# LWOC_PCB_2v1.net
KiCad netlist of a schematic drawn in EAGLE
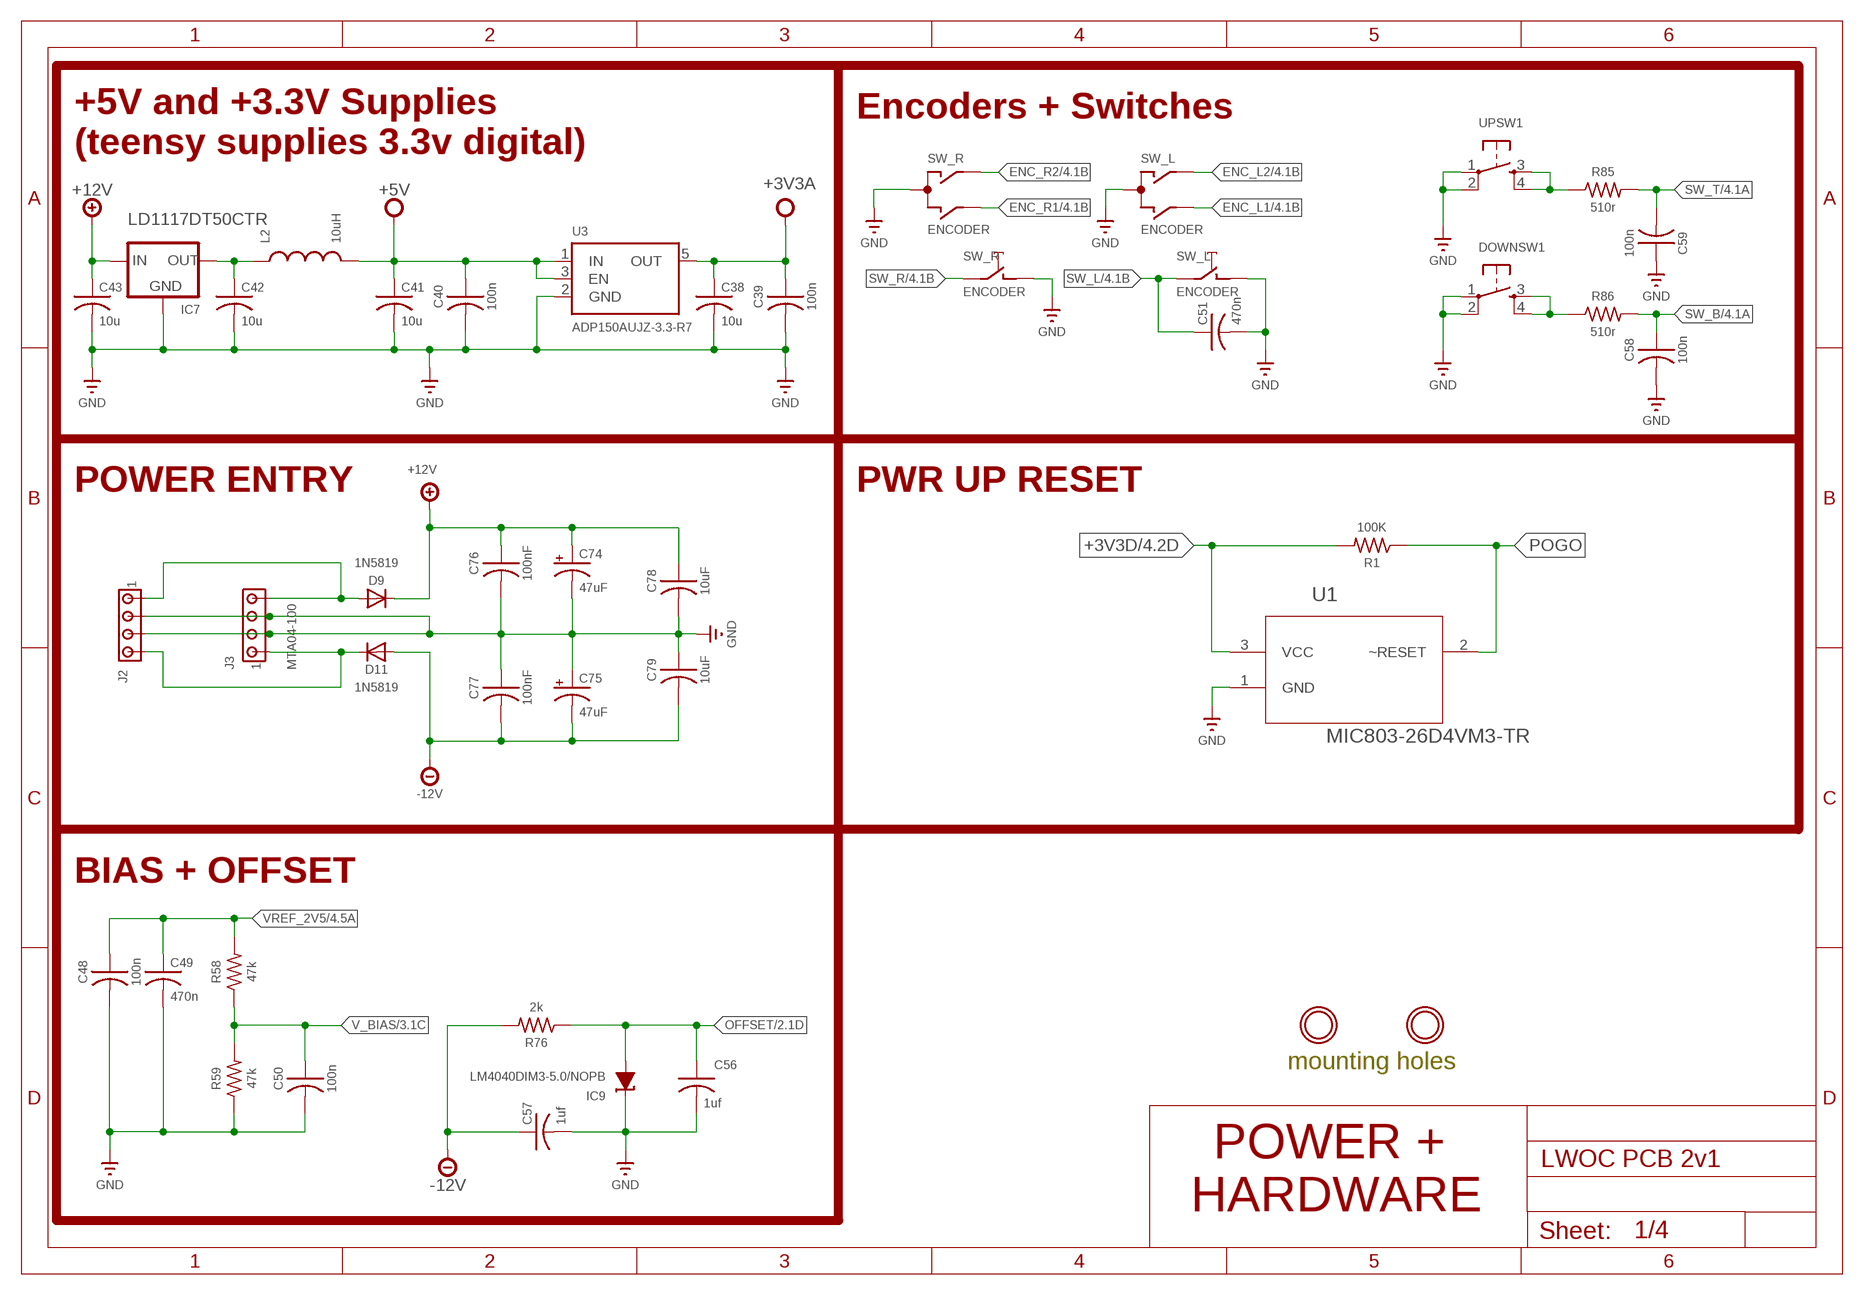
[diagram p0: schematic, sheet 1]
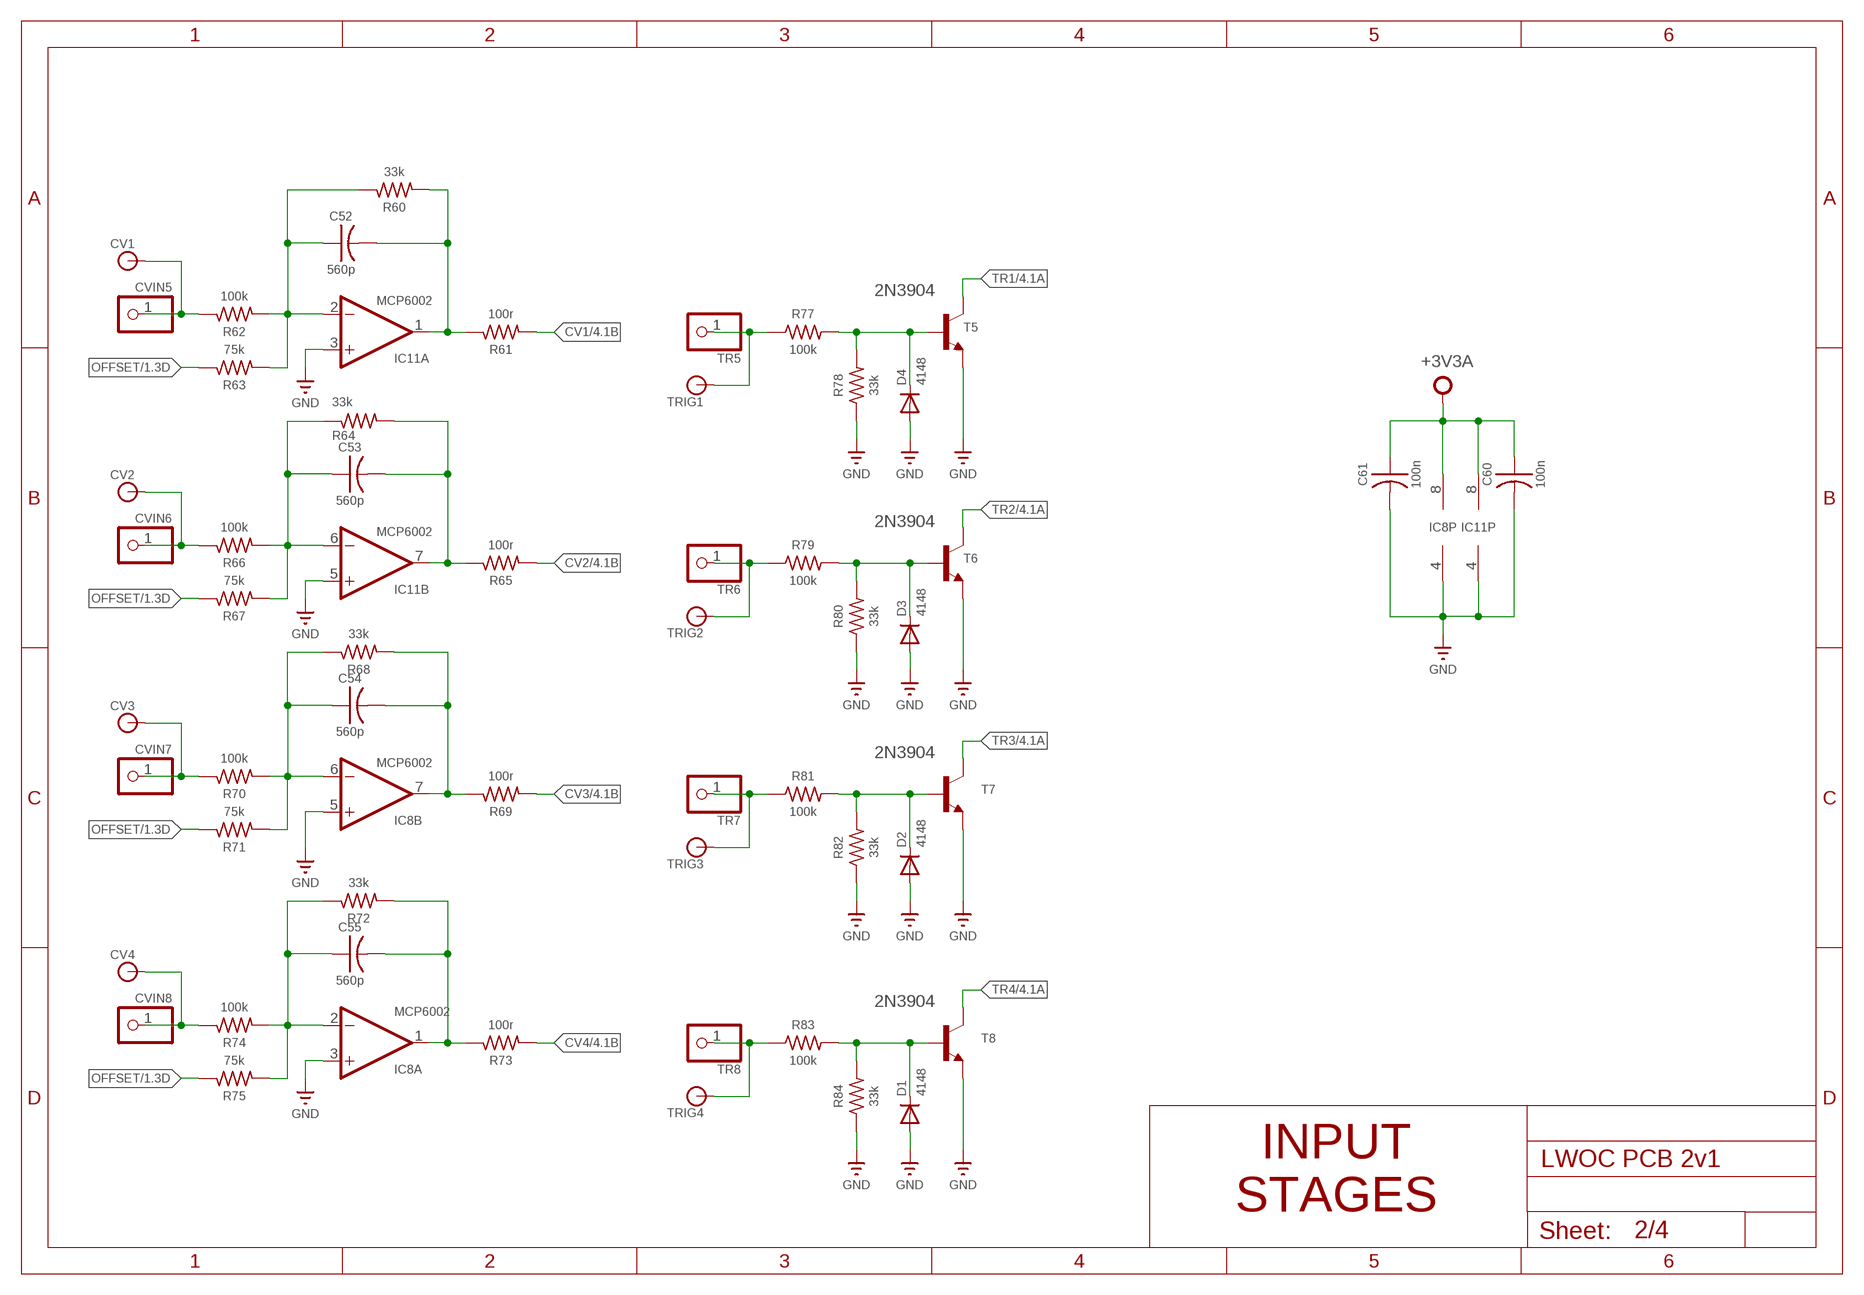
[diagram p1: schematic, sheet 2]
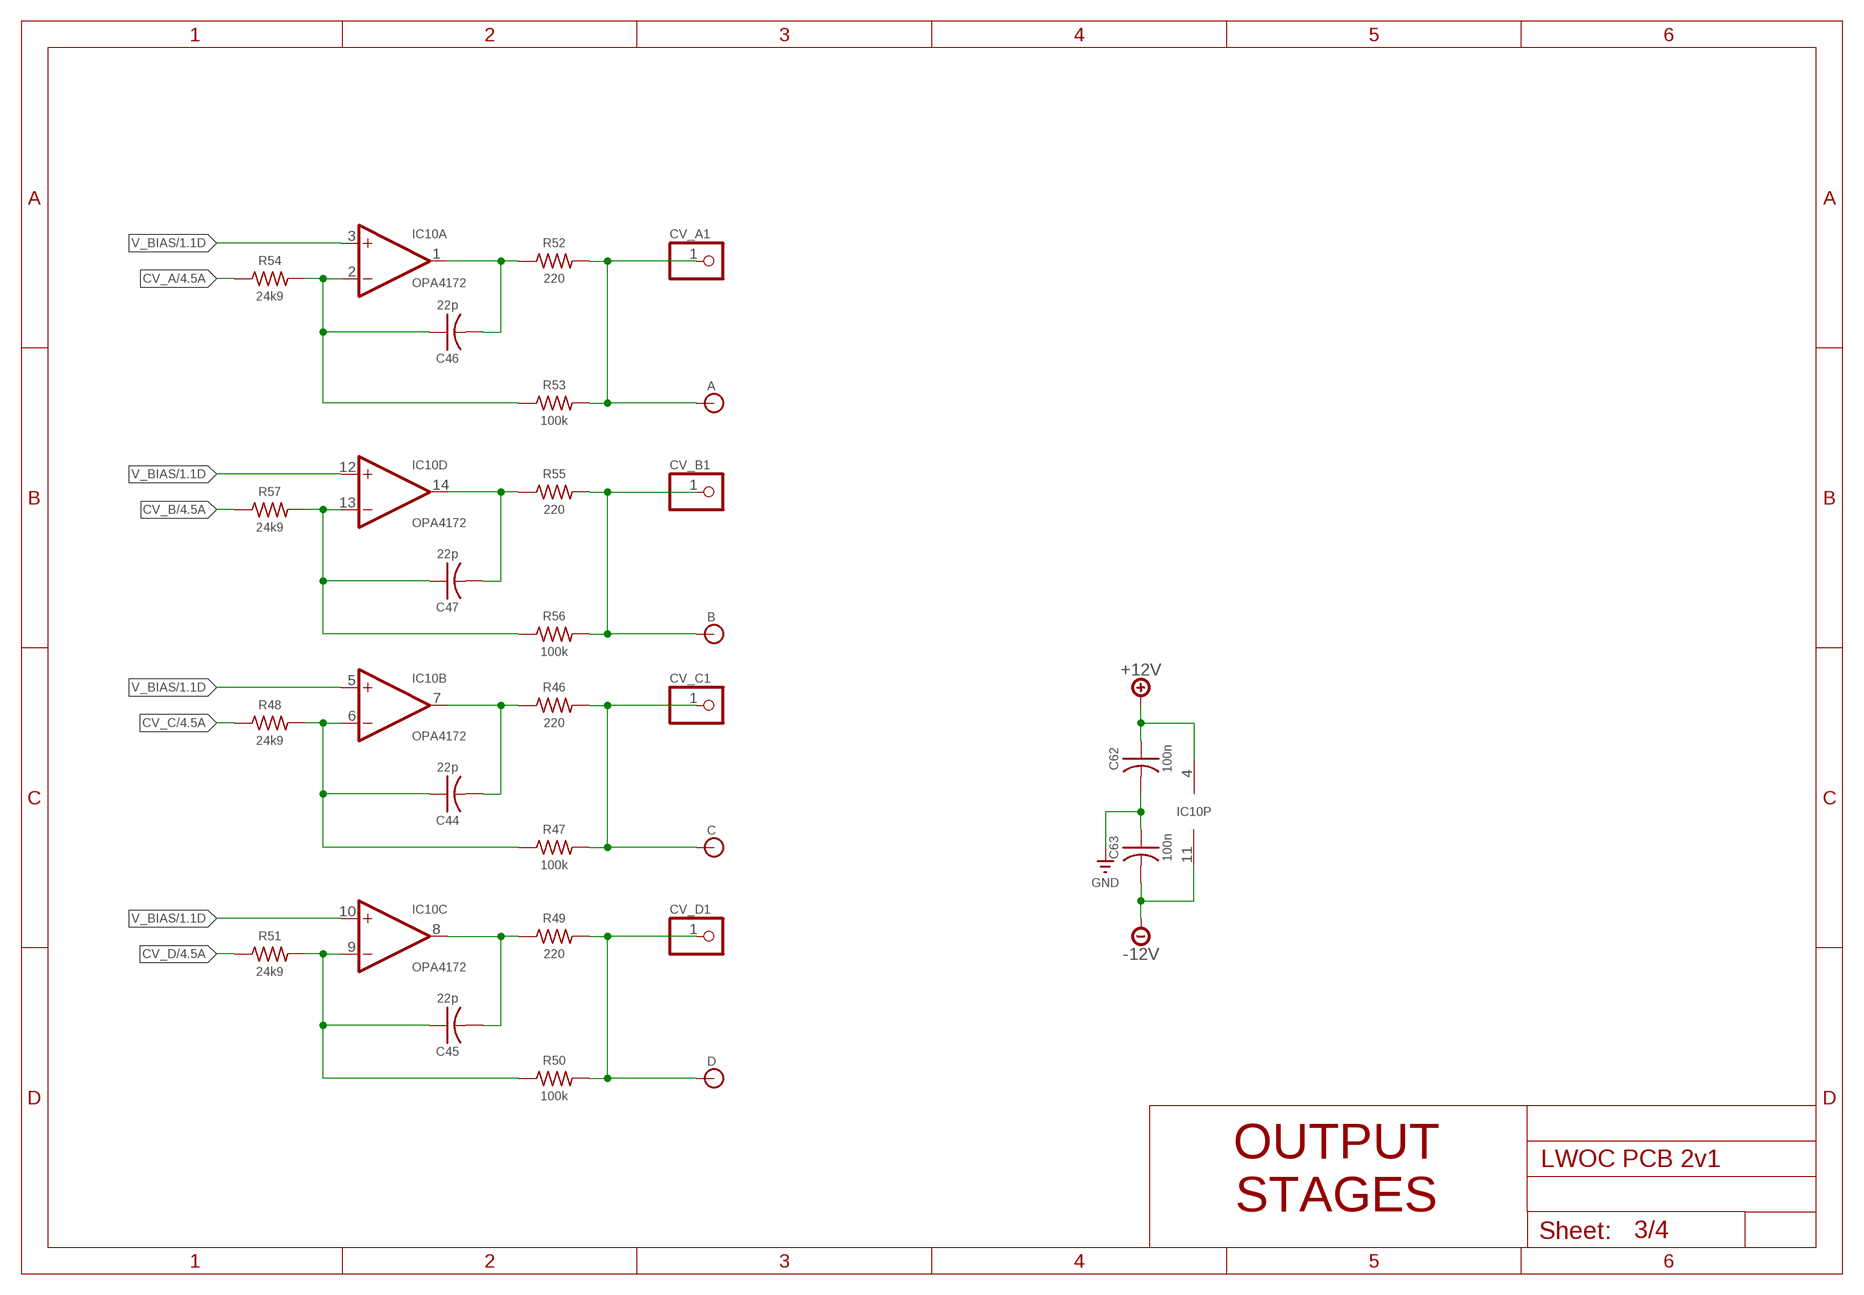
[diagram p2: schematic, sheet 3]
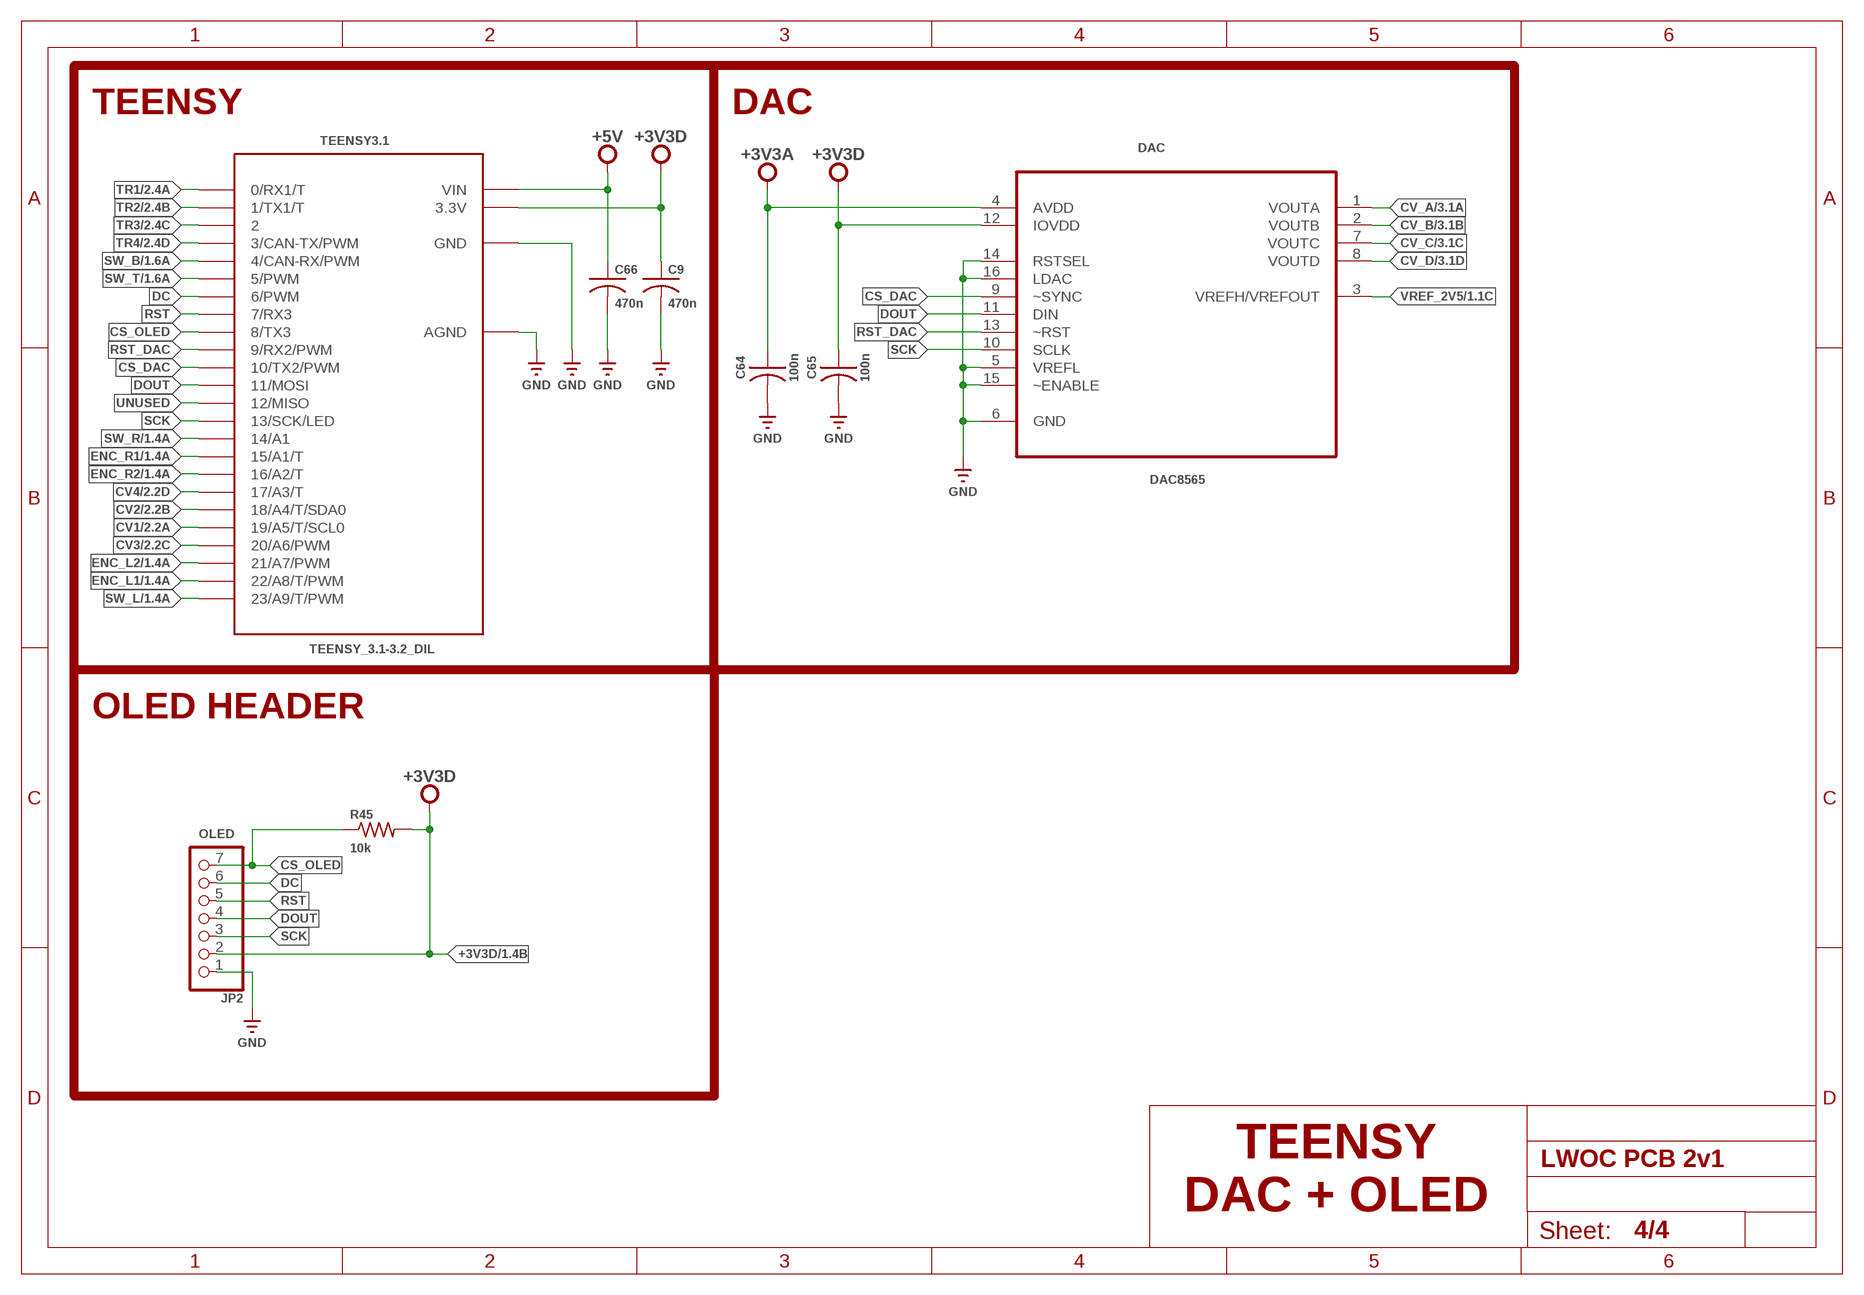
[diagram p3: schematic, sheet 4]

(export (version "E")
  (design (tool "Eeschema 10.0.6"))
  (components
    (comp (ref "C38")
      (value "10u")
      (footprint "eagle-import:C1206K")
      (libsource (lib "eagle-import") (part "C-USC1206K"))
    )
    (comp (ref "C39")
      (value "100n")
      (footprint "eagle-import:RCL_C0603K")
      (libsource (lib "eagle-import") (part "RCL_C-USC0603K"))
    )
    (comp (ref "C40")
      (value "100n")
      (footprint "eagle-import:RCL_C0603K")
      (libsource (lib "eagle-import") (part "RCL_C-USC0603K"))
    )
    (comp (ref "C41")
      (value "10u")
      (footprint "eagle-import:C1206K")
      (libsource (lib "eagle-import") (part "C-USC1206K"))
    )
    (comp (ref "C42")
      (value "10u")
      (footprint "eagle-import:C1206K")
      (libsource (lib "eagle-import") (part "C-USC1206K"))
    )
    (comp (ref "C43")
      (value "10u")
      (footprint "eagle-import:C1206K")
      (libsource (lib "eagle-import") (part "C-USC1206K"))
    )
    (comp (ref "C48")
      (value "100n")
      (footprint "eagle-import:RCL_C0603K")
      (libsource (lib "eagle-import") (part "RCL_C-USC0603K"))
    )
    (comp (ref "C49")
      (value "470n")
      (footprint "eagle-import:RCL_C0603K")
      (libsource (lib "eagle-import") (part "RCL_C-USC0603K"))
    )
    (comp (ref "C50")
      (value "100n")
      (footprint "eagle-import:RCL_C0603K")
      (libsource (lib "eagle-import") (part "RCL_C-USC0603K"))
    )
    (comp (ref "C51")
      (value "470n")
      (footprint "eagle-import:C0805K")
      (libsource (lib "eagle-import") (part "C-USC0805K"))
    )
    (comp (ref "C56")
      (value "1uf")
      (footprint "eagle-import:C0805K")
      (libsource (lib "eagle-import") (part "C-USC0805K"))
    )
    (comp (ref "C57")
      (value "1uf")
      (footprint "eagle-import:C0805K")
      (libsource (lib "eagle-import") (part "C-USC0805K"))
    )
    (comp (ref "C58")
      (value "100n")
      (footprint "eagle-import:RCL_C0603K")
      (libsource (lib "eagle-import") (part "RCL_C-USC0603K"))
    )
    (comp (ref "C59")
      (value "100n")
      (footprint "eagle-import:RCL_C0603K")
      (libsource (lib "eagle-import") (part "RCL_C-USC0603K"))
    )
    (comp (ref "C74")
      (value "47uF")
      (footprint "eagle-import:RCL_E2,5-6")
      (libsource (lib "eagle-import") (part "RCL_CPOL-USE2.5-6"))
    )
    (comp (ref "C75")
      (value "47uF")
      (footprint "eagle-import:RCL_E2,5-6")
      (libsource (lib "eagle-import") (part "RCL_CPOL-USE2.5-6"))
    )
    (comp (ref "C76")
      (value "100nF")
      (footprint "eagle-import:RCL_C0603K")
      (libsource (lib "eagle-import") (part "ripples_v40_RCL_C-USC0603K"))
    )
    (comp (ref "C77")
      (value "100nF")
      (footprint "eagle-import:RCL_C0603K")
      (libsource (lib "eagle-import") (part "ripples_v40_RCL_C-USC0603K"))
    )
    (comp (ref "C78")
      (value "10uF")
      (footprint "eagle-import:RCL_C1210")
      (libsource (lib "eagle-import") (part "RCL_C-USC1210"))
    )
    (comp (ref "C79")
      (value "10uF")
      (footprint "eagle-import:RCL_C1210")
      (libsource (lib "eagle-import") (part "RCL_C-USC1210"))
    )
    (comp (ref "D9")
      (value "1N5819")
      (footprint "eagle-import:DIODE_SOD323-W")
      (libsource (lib "eagle-import") (part "ripples_v40_DIODE_DIODE-SOD323-W"))
    )
    (comp (ref "D11")
      (value "1N5819")
      (footprint "eagle-import:DIODE_SOD323-W")
      (libsource (lib "eagle-import") (part "ripples_v40_DIODE_DIODE-SOD323-W"))
    )
    (comp (ref "DOWNSW1")
      (value "SPARKFUN_TAC_SWITCHPTH")
      (footprint "eagle-import:SPARKFUN_TACTILE-PTH")
      (libsource (lib "eagle-import") (part "SPARKFUN_TAC_SWITCHPTH"))
    )
    (comp (ref "IC7")
      (value "LD1117DT50CTR")
      (footprint "eagle-import:TO252")
      (libsource (lib "eagle-import") (part "LM1117TO252"))
    )
    (comp (ref "IC9")
      (value "LM4040DIM3-5.0/NOPB")
      (footprint "eagle-import:DBZ_R-PDSO-G3")
      (libsource (lib "eagle-import") (part "LM4041DBZA12"))
    )
    (comp (ref "J2")
      (value "MTA04-156")
      (footprint "eagle-import:1X4MTA")
      (libsource (lib "eagle-import") (part "MTA04-156"))
    )
    (comp (ref "J3")
      (value "MTA04-100")
      (footprint "eagle-import:1X04MTA")
      (libsource (lib "eagle-import") (part "MTA04-100"))
    )
    (comp (ref "L2")
      (value "10uH")
      (footprint "eagle-import:1210")
      (libsource (lib "eagle-import") (part "INDUCTOR1210"))
    )
    (comp (ref "R1")
      (value "100K")
      (footprint "eagle-import:RCL_R0603")
      (libsource (lib "eagle-import") (part "RCL_R-US_R0603"))
    )
    (comp (ref "R58")
      (value "47k")
      (footprint "eagle-import:RCL_R0603")
      (libsource (lib "eagle-import") (part "RCL_R-US_R0603"))
    )
    (comp (ref "R59")
      (value "47k")
      (footprint "eagle-import:RCL_R0603")
      (libsource (lib "eagle-import") (part "RCL_R-US_R0603"))
    )
    (comp (ref "R76")
      (value "2k")
      (footprint "eagle-import:RCL_R0603")
      (libsource (lib "eagle-import") (part "RCL_R-US_R0603"))
    )
    (comp (ref "R85")
      (value "510r")
      (footprint "eagle-import:RCL_R0603")
      (libsource (lib "eagle-import") (part "RCL_R-US_R0603"))
    )
    (comp (ref "R86")
      (value "510r")
      (footprint "eagle-import:RCL_R0603")
      (libsource (lib "eagle-import") (part "RCL_R-US_R0603"))
    )
    (comp (ref "SW_L")
      (value "ENCODER")
      (footprint "eagle-import:OG-ENCODER_ALPS_EC12E_SW")
      (libsource (lib "eagle-import") (part "OG-ENCODER_EC12E_SW"))
    )
    (comp (ref "SW_R")
      (value "ENCODER")
      (footprint "eagle-import:OG-ENCODER_ALPS_EC12E_SW")
      (libsource (lib "eagle-import") (part "OG-ENCODER_EC12E_SW"))
    )
    (comp (ref "U$23")
      (value "MOUNTINGHOLE2.5")
      (footprint "eagle-import:MOUNTINGHOLE_2.5_PLATED")
      (libsource (lib "eagle-import") (part "MOUNTINGHOLE2.5"))
    )
    (comp (ref "U$26")
      (value "MOUNTINGHOLE2.5")
      (footprint "eagle-import:MOUNTINGHOLE_2.5_PLATED")
      (libsource (lib "eagle-import") (part "MOUNTINGHOLE2.5"))
    )
    (comp (ref "U1")
      (value "MIC803-26D4VM3-TR")
      (footprint "eagle-import:SOT95P232X110-3N")
      (fields (field (name "MPN") "MIC803-30D4VM3TR"))
      (libsource (lib "eagle-import") (part "MIC803-30D4VM3TR"))
    )
    (comp (ref "U3")
      (value "ADP150AUJZ-3.3-R7")
      (footprint "eagle-import:SOT23-5")
      (libsource (lib "eagle-import") (part "ADP121"))
    )
    (comp (ref "UPSW1")
      (value "SPARKFUN_TAC_SWITCHPTH")
      (footprint "eagle-import:SPARKFUN_TACTILE-PTH")
      (libsource (lib "eagle-import") (part "SPARKFUN_TAC_SWITCHPTH"))
    )
    (comp (ref "C9")
      (value "470n")
      (footprint "eagle-import:C0805K")
      (libsource (lib "eagle-import") (part "C-USC0805K"))
    )
    (comp (ref "C64")
      (value "100n")
      (footprint "eagle-import:RCL_C0603K")
      (libsource (lib "eagle-import") (part "RCL_C-USC0603K"))
    )
    (comp (ref "C65")
      (value "100n")
      (footprint "eagle-import:RCL_C0603K")
      (libsource (lib "eagle-import") (part "RCL_C-USC0603K"))
    )
    (comp (ref "C66")
      (value "470n")
      (footprint "eagle-import:C0805K")
      (libsource (lib "eagle-import") (part "C-USC0805K"))
    )
    (comp (ref "DAC")
      (value "DAC8565")
      (footprint "eagle-import:SOP65P640X120-16N")
      (fields (field (name "MF") "Texas Instruments") (field (name "MP") "DAC8565IAPW"))
      (libsource (lib "eagle-import") (part "DAC8565IAPW"))
    )
    (comp (ref "JP2")
      (value "OLED")
      (footprint "eagle-import:1X07-S")
      (libsource (lib "eagle-import") (part "PINHD-1X07_2.54-S"))
    )
    (comp (ref "R45")
      (value "10k")
      (footprint "eagle-import:M0805")
      (libsource (lib "eagle-import") (part "R-US_M0805"))
    )
    (comp (ref "TEENSY3.1")
      (value "TEENSY_3.1-3.2_DIL")
      (footprint "eagle-import:TEENSY_3.0-3.2&LC_DIL")
      (libsource (lib "eagle-import") (part "TEENSY_3.1-3.2_DIL"))
    )
    (comp (ref "C52")
      (value "560p")
      (footprint "eagle-import:RCL_C0603K")
      (libsource (lib "eagle-import") (part "RCL_C-USC0603K"))
    )
    (comp (ref "C53")
      (value "560p")
      (footprint "eagle-import:RCL_C0603K")
      (libsource (lib "eagle-import") (part "RCL_C-USC0603K"))
    )
    (comp (ref "C54")
      (value "560p")
      (footprint "eagle-import:RCL_C0603K")
      (libsource (lib "eagle-import") (part "RCL_C-USC0603K"))
    )
    (comp (ref "C55")
      (value "560p")
      (footprint "eagle-import:RCL_C0603K")
      (libsource (lib "eagle-import") (part "RCL_C-USC0603K"))
    )
    (comp (ref "C60")
      (value "100n")
      (footprint "eagle-import:RCL_C0603K")
      (libsource (lib "eagle-import") (part "RCL_C-USC0603K"))
    )
    (comp (ref "C61")
      (value "100n")
      (footprint "eagle-import:RCL_C0603K")
      (libsource (lib "eagle-import") (part "RCL_C-USC0603K"))
    )
    (comp (ref "CV1")
      (value "BANANA_CONN")
      (footprint "eagle-import:BANANA_CONN")
      (libsource (lib "eagle-import") (part "BANANA_CONN"))
    )
    (comp (ref "CV2")
      (value "BANANA_CONN")
      (footprint "eagle-import:BANANA_CONN")
      (libsource (lib "eagle-import") (part "BANANA_CONN"))
    )
    (comp (ref "CV3")
      (value "BANANA_CONN")
      (footprint "eagle-import:BANANA_CONN")
      (libsource (lib "eagle-import") (part "BANANA_CONN"))
    )
    (comp (ref "CV4")
      (value "BANANA_CONN")
      (footprint "eagle-import:BANANA_CONN")
      (libsource (lib "eagle-import") (part "BANANA_CONN"))
    )
    (comp (ref "CVIN5")
      (value "PINHD-1X1")
      (footprint "eagle-import:1X01")
      (libsource (lib "eagle-import") (part "PINHD-1X1"))
    )
    (comp (ref "CVIN6")
      (value "PINHD-1X1")
      (footprint "eagle-import:1X01")
      (libsource (lib "eagle-import") (part "PINHD-1X1"))
    )
    (comp (ref "CVIN7")
      (value "PINHD-1X1")
      (footprint "eagle-import:1X01")
      (libsource (lib "eagle-import") (part "PINHD-1X1"))
    )
    (comp (ref "CVIN8")
      (value "PINHD-1X1")
      (footprint "eagle-import:1X01")
      (libsource (lib "eagle-import") (part "PINHD-1X1"))
    )
    (comp (ref "D1")
      (value "4148")
      (footprint "eagle-import:DIODE_SOD323-W")
      (libsource (lib "eagle-import") (part "DIODE_DIODE-SOD323-W"))
    )
    (comp (ref "D2")
      (value "4148")
      (footprint "eagle-import:DIODE_SOD323-W")
      (libsource (lib "eagle-import") (part "DIODE_DIODE-SOD323-W"))
    )
    (comp (ref "D3")
      (value "4148")
      (footprint "eagle-import:DIODE_SOD323-W")
      (libsource (lib "eagle-import") (part "DIODE_DIODE-SOD323-W"))
    )
    (comp (ref "D4")
      (value "4148")
      (footprint "eagle-import:DIODE_SOD323-W")
      (libsource (lib "eagle-import") (part "DIODE_DIODE-SOD323-W"))
    )
    (comp (ref "IC8")
      (value "MCP6002")
      (footprint "eagle-import:GM-ICS_SO08")
      (libsource (lib "eagle-import") (part "GM-ICS_TL072D"))
    )
    (comp (ref "IC11")
      (value "MCP6002")
      (footprint "eagle-import:GM-ICS_SO08")
      (libsource (lib "eagle-import") (part "GM-ICS_TL072D"))
    )
    (comp (ref "R60")
      (value "33k")
      (footprint "eagle-import:RCL_R0603")
      (libsource (lib "eagle-import") (part "RCL_R-US_R0603"))
    )
    (comp (ref "R61")
      (value "100r")
      (footprint "eagle-import:RCL_R0603")
      (libsource (lib "eagle-import") (part "RCL_R-US_R0603"))
    )
    (comp (ref "R62")
      (value "100k")
      (footprint "eagle-import:RCL_R0603")
      (libsource (lib "eagle-import") (part "RCL_R-US_R0603"))
    )
    (comp (ref "R63")
      (value "75k")
      (footprint "eagle-import:RCL_R0603")
      (libsource (lib "eagle-import") (part "RCL_R-US_R0603"))
    )
    (comp (ref "R64")
      (value "33k")
      (footprint "eagle-import:RCL_R0603")
      (libsource (lib "eagle-import") (part "RCL_R-US_R0603"))
    )
    (comp (ref "R65")
      (value "100r")
      (footprint "eagle-import:RCL_R0603")
      (libsource (lib "eagle-import") (part "RCL_R-US_R0603"))
    )
    (comp (ref "R66")
      (value "100k")
      (footprint "eagle-import:RCL_R0603")
      (libsource (lib "eagle-import") (part "RCL_R-US_R0603"))
    )
    (comp (ref "R67")
      (value "75k")
      (footprint "eagle-import:RCL_R0603")
      (libsource (lib "eagle-import") (part "RCL_R-US_R0603"))
    )
    (comp (ref "R68")
      (value "33k")
      (footprint "eagle-import:RCL_R0603")
      (libsource (lib "eagle-import") (part "RCL_R-US_R0603"))
    )
    (comp (ref "R69")
      (value "100r")
      (footprint "eagle-import:RCL_R0603")
      (libsource (lib "eagle-import") (part "RCL_R-US_R0603"))
    )
    (comp (ref "R70")
      (value "100k")
      (footprint "eagle-import:RCL_R0603")
      (libsource (lib "eagle-import") (part "RCL_R-US_R0603"))
    )
    (comp (ref "R71")
      (value "75k")
      (footprint "eagle-import:RCL_R0603")
      (libsource (lib "eagle-import") (part "RCL_R-US_R0603"))
    )
    (comp (ref "R72")
      (value "33k")
      (footprint "eagle-import:RCL_R0603")
      (libsource (lib "eagle-import") (part "RCL_R-US_R0603"))
    )
    (comp (ref "R73")
      (value "100r")
      (footprint "eagle-import:RCL_R0603")
      (libsource (lib "eagle-import") (part "RCL_R-US_R0603"))
    )
    (comp (ref "R74")
      (value "100k")
      (footprint "eagle-import:RCL_R0603")
      (libsource (lib "eagle-import") (part "RCL_R-US_R0603"))
    )
    (comp (ref "R75")
      (value "75k")
      (footprint "eagle-import:RCL_R0603")
      (libsource (lib "eagle-import") (part "RCL_R-US_R0603"))
    )
    (comp (ref "R77")
      (value "100k")
      (footprint "eagle-import:RCL_R0603")
      (libsource (lib "eagle-import") (part "RCL_R-US_R0603"))
    )
    (comp (ref "R78")
      (value "33k")
      (footprint "eagle-import:RCL_R0603")
      (libsource (lib "eagle-import") (part "RCL_R-US_R0603"))
    )
    (comp (ref "R79")
      (value "100k")
      (footprint "eagle-import:RCL_R0603")
      (libsource (lib "eagle-import") (part "RCL_R-US_R0603"))
    )
    (comp (ref "R80")
      (value "33k")
      (footprint "eagle-import:RCL_R0603")
      (libsource (lib "eagle-import") (part "RCL_R-US_R0603"))
    )
    (comp (ref "R81")
      (value "100k")
      (footprint "eagle-import:RCL_R0603")
      (libsource (lib "eagle-import") (part "RCL_R-US_R0603"))
    )
    (comp (ref "R82")
      (value "33k")
      (footprint "eagle-import:RCL_R0603")
      (libsource (lib "eagle-import") (part "RCL_R-US_R0603"))
    )
    (comp (ref "R83")
      (value "100k")
      (footprint "eagle-import:RCL_R0603")
      (libsource (lib "eagle-import") (part "RCL_R-US_R0603"))
    )
    (comp (ref "R84")
      (value "33k")
      (footprint "eagle-import:RCL_R0603")
      (libsource (lib "eagle-import") (part "RCL_R-US_R0603"))
    )
    (comp (ref "T5")
      (value "2N3904")
      (footprint "eagle-import:TRANSISTOR_SOT23-BEC")
      (libsource (lib "eagle-import") (part "TRANSISTOR_-NPN-SOT23-BECMMBT3904LT1"))
    )
    (comp (ref "T6")
      (value "2N3904")
      (footprint "eagle-import:TRANSISTOR_SOT23-BEC")
      (libsource (lib "eagle-import") (part "TRANSISTOR_-NPN-SOT23-BECMMBT3904LT1"))
    )
    (comp (ref "T7")
      (value "2N3904")
      (footprint "eagle-import:TRANSISTOR_SOT23-BEC")
      (libsource (lib "eagle-import") (part "TRANSISTOR_-NPN-SOT23-BECMMBT3904LT1"))
    )
    (comp (ref "T8")
      (value "2N3904")
      (footprint "eagle-import:TRANSISTOR_SOT23-BEC")
      (libsource (lib "eagle-import") (part "TRANSISTOR_-NPN-SOT23-BECMMBT3904LT1"))
    )
    (comp (ref "TR5")
      (value "PINHD-1X1")
      (footprint "eagle-import:1X01")
      (libsource (lib "eagle-import") (part "PINHD-1X1"))
    )
    (comp (ref "TR6")
      (value "PINHD-1X1")
      (footprint "eagle-import:1X01")
      (libsource (lib "eagle-import") (part "PINHD-1X1"))
    )
    (comp (ref "TR7")
      (value "PINHD-1X1")
      (footprint "eagle-import:1X01")
      (libsource (lib "eagle-import") (part "PINHD-1X1"))
    )
    (comp (ref "TR8")
      (value "PINHD-1X1")
      (footprint "eagle-import:1X01")
      (libsource (lib "eagle-import") (part "PINHD-1X1"))
    )
    (comp (ref "TRIG1")
      (value "BANANA_CONN")
      (footprint "eagle-import:BANANA_CONN")
      (libsource (lib "eagle-import") (part "BANANA_CONN"))
    )
    (comp (ref "TRIG2")
      (value "BANANA_CONN")
      (footprint "eagle-import:BANANA_CONN")
      (libsource (lib "eagle-import") (part "BANANA_CONN"))
    )
    (comp (ref "TRIG3")
      (value "BANANA_CONN")
      (footprint "eagle-import:BANANA_CONN")
      (libsource (lib "eagle-import") (part "BANANA_CONN"))
    )
    (comp (ref "TRIG4")
      (value "BANANA_CONN")
      (footprint "eagle-import:BANANA_CONN")
      (libsource (lib "eagle-import") (part "BANANA_CONN"))
    )
    (comp (ref "A")
      (value "BANANA_CONN")
      (footprint "eagle-import:BANANA_CONN")
      (libsource (lib "eagle-import") (part "BANANA_CONN"))
    )
    (comp (ref "B")
      (value "BANANA_CONN")
      (footprint "eagle-import:BANANA_CONN")
      (libsource (lib "eagle-import") (part "BANANA_CONN"))
    )
    (comp (ref "C")
      (value "BANANA_CONN")
      (footprint "eagle-import:BANANA_CONN")
      (libsource (lib "eagle-import") (part "BANANA_CONN"))
    )
    (comp (ref "C44")
      (value "22p")
      (footprint "eagle-import:RCL_C0603K")
      (libsource (lib "eagle-import") (part "RCL_C-USC0603K"))
    )
    (comp (ref "C45")
      (value "22p")
      (footprint "eagle-import:RCL_C0603K")
      (libsource (lib "eagle-import") (part "RCL_C-USC0603K"))
    )
    (comp (ref "C46")
      (value "22p")
      (footprint "eagle-import:RCL_C0603K")
      (libsource (lib "eagle-import") (part "RCL_C-USC0603K"))
    )
    (comp (ref "C47")
      (value "22p")
      (footprint "eagle-import:RCL_C0603K")
      (libsource (lib "eagle-import") (part "RCL_C-USC0603K"))
    )
    (comp (ref "C62")
      (value "100n")
      (footprint "eagle-import:RCL_C0603K")
      (libsource (lib "eagle-import") (part "RCL_C-USC0603K"))
    )
    (comp (ref "C63")
      (value "100n")
      (footprint "eagle-import:RCL_C0603K")
      (libsource (lib "eagle-import") (part "RCL_C-USC0603K"))
    )
    (comp (ref "CV_A1")
      (value "PINHD-1X1")
      (footprint "eagle-import:1X01")
      (libsource (lib "eagle-import") (part "PINHD-1X1"))
    )
    (comp (ref "CV_B1")
      (value "PINHD-1X1")
      (footprint "eagle-import:1X01")
      (libsource (lib "eagle-import") (part "PINHD-1X1"))
    )
    (comp (ref "CV_C1")
      (value "PINHD-1X1")
      (footprint "eagle-import:1X01")
      (libsource (lib "eagle-import") (part "PINHD-1X1"))
    )
    (comp (ref "CV_D1")
      (value "PINHD-1X1")
      (footprint "eagle-import:1X01")
      (libsource (lib "eagle-import") (part "PINHD-1X1"))
    )
    (comp (ref "D")
      (value "BANANA_CONN")
      (footprint "eagle-import:BANANA_CONN")
      (libsource (lib "eagle-import") (part "BANANA_CONN"))
    )
    (comp (ref "IC10")
      (value "OPA4172")
      (footprint "eagle-import:GM-ICS_SO14")
      (libsource (lib "eagle-import") (part "GM-ICS_TL074D"))
    )
    (comp (ref "R46")
      (value "220")
      (footprint "eagle-import:RCL_R0603")
      (libsource (lib "eagle-import") (part "RCL_R-US_R0603"))
    )
    (comp (ref "R47")
      (value "100k")
      (footprint "eagle-import:RCL_R0603")
      (libsource (lib "eagle-import") (part "RCL_R-US_R0603"))
    )
    (comp (ref "R48")
      (value "24k9")
      (footprint "eagle-import:RCL_R0603")
      (libsource (lib "eagle-import") (part "RCL_R-US_R0603"))
    )
    (comp (ref "R49")
      (value "220")
      (footprint "eagle-import:RCL_R0603")
      (libsource (lib "eagle-import") (part "RCL_R-US_R0603"))
    )
    (comp (ref "R50")
      (value "100k")
      (footprint "eagle-import:RCL_R0603")
      (libsource (lib "eagle-import") (part "RCL_R-US_R0603"))
    )
    (comp (ref "R51")
      (value "24k9")
      (footprint "eagle-import:RCL_R0603")
      (libsource (lib "eagle-import") (part "RCL_R-US_R0603"))
    )
    (comp (ref "R52")
      (value "220")
      (footprint "eagle-import:RCL_R0603")
      (libsource (lib "eagle-import") (part "RCL_R-US_R0603"))
    )
    (comp (ref "R53")
      (value "100k")
      (footprint "eagle-import:RCL_R0603")
      (libsource (lib "eagle-import") (part "RCL_R-US_R0603"))
    )
    (comp (ref "R54")
      (value "24k9")
      (footprint "eagle-import:RCL_R0603")
      (libsource (lib "eagle-import") (part "RCL_R-US_R0603"))
    )
    (comp (ref "R55")
      (value "220")
      (footprint "eagle-import:RCL_R0603")
      (libsource (lib "eagle-import") (part "RCL_R-US_R0603"))
    )
    (comp (ref "R56")
      (value "100k")
      (footprint "eagle-import:RCL_R0603")
      (libsource (lib "eagle-import") (part "RCL_R-US_R0603"))
    )
    (comp (ref "R57")
      (value "24k9")
      (footprint "eagle-import:RCL_R0603")
      (libsource (lib "eagle-import") (part "RCL_R-US_R0603"))
    )
  )
  (nets
    (net (code "1") (name "+3V3A") (class "Default")
      (node (ref "C38") (pin "1") (pinfunction "1_1") (pintype "passive"))
      (node (ref "C39") (pin "1") (pinfunction "1_1") (pintype "passive"))
      (node (ref "C60") (pin "1") (pinfunction "1_1") (pintype "passive"))
      (node (ref "C61") (pin "1") (pinfunction "1_1") (pintype "passive"))
      (node (ref "C64") (pin "1") (pinfunction "1_1") (pintype "passive"))
      (node (ref "DAC") (pin "4") (pinfunction "AVDD_4") (pintype "power_in"))
      (node (ref "IC11") (pin "8") (pinfunction "V+_8") (pintype "power_in"))
      (node (ref "IC8") (pin "8") (pinfunction "V+_8") (pintype "power_in"))
      (node (ref "U3") (pin "5") (pinfunction "OUT_5") (pintype "bidirectional"))
    )
    (net (code "2") (name "+3V3D") (class "Default")
      (node (ref "C65") (pin "1") (pinfunction "1_1") (pintype "passive"))
      (node (ref "C9") (pin "1") (pinfunction "1_1") (pintype "passive"))
      (node (ref "DAC") (pin "12") (pinfunction "IOVDD_12") (pintype "power_in"))
      (node (ref "JP2") (pin "2") (pinfunction "2_2") (pintype "passive"))
      (node (ref "R1") (pin "2") (pinfunction "2_2") (pintype "passive"))
      (node (ref "R45") (pin "2") (pinfunction "2_2") (pintype "passive"))
      (node (ref "TEENSY3.1") (pin "3.3V") (pinfunction "3.3V_3.3V") (pintype "power_in"))
      (node (ref "U1") (pin "3") (pinfunction "VCC_3") (pintype "power_in"))
    )
    (net (code "3") (name "+5V") (class "Default")
      (node (ref "C40") (pin "1") (pinfunction "1_1") (pintype "passive"))
      (node (ref "C41") (pin "1") (pinfunction "1_1") (pintype "passive"))
      (node (ref "C66") (pin "1") (pinfunction "1_1") (pintype "passive"))
      (node (ref "L2") (pin "2") (pinfunction "2_2") (pintype "passive"))
      (node (ref "TEENSY3.1") (pin "VIN") (pinfunction "VIN_VIN") (pintype "power_in"))
      (node (ref "U3") (pin "1") (pinfunction "IN_1") (pintype "bidirectional"))
      (node (ref "U3") (pin "3") (pinfunction "EN_3") (pintype "bidirectional"))
    )
    (net (code "4") (name "+12V") (class "Default")
      (node (ref "C43") (pin "1") (pinfunction "1_1") (pintype "passive"))
      (node (ref "C62") (pin "1") (pinfunction "1_1") (pintype "passive"))
      (node (ref "C74") (pin "+") (pinfunction "+_+") (pintype "passive"))
      (node (ref "C76") (pin "1") (pinfunction "1_1") (pintype "passive"))
      (node (ref "C78") (pin "1") (pinfunction "1_1") (pintype "passive"))
      (node (ref "D9") (pin "C") (pinfunction "C_C") (pintype "passive"))
      (node (ref "IC10") (pin "4") (pinfunction "V+_4") (pintype "power_in"))
      (node (ref "IC7") (pin "2") (pinfunction "IN_2") (pintype "input"))
    )
    (net (code "5") (name "-12V") (class "Default")
      (node (ref "C57") (pin "1") (pinfunction "1_1") (pintype "passive"))
      (node (ref "C63") (pin "2") (pinfunction "2_2") (pintype "passive"))
      (node (ref "C75") (pin "-") (pinfunction "-_-") (pintype "passive"))
      (node (ref "C77") (pin "2") (pinfunction "2_2") (pintype "passive"))
      (node (ref "C79") (pin "2") (pinfunction "2_2") (pintype "passive"))
      (node (ref "D11") (pin "A") (pinfunction "A_A") (pintype "passive"))
      (node (ref "IC10") (pin "11") (pinfunction "V-_11") (pintype "power_in"))
      (node (ref "R76") (pin "2") (pinfunction "2_2") (pintype "passive"))
    )
    (net (code "6") (name "CS_DAC") (class "Default")
      (node (ref "DAC") (pin "9") (pinfunction "~{SYNC}_9") (pintype "input"))
      (node (ref "TEENSY3.1") (pin "10") (pinfunction "10/TX2/PWM_10") (pintype "bidirectional"))
    )
    (net (code "7") (name "CS_OLED") (class "Default")
      (node (ref "JP2") (pin "7") (pinfunction "7_7") (pintype "passive"))
      (node (ref "R45") (pin "1") (pinfunction "1_1") (pintype "passive"))
      (node (ref "TEENSY3.1") (pin "8") (pinfunction "8/TX3_8") (pintype "bidirectional"))
    )
    (net (code "8") (name "CV1") (class "Default")
      (node (ref "R61") (pin "2") (pinfunction "2_2") (pintype "passive"))
      (node (ref "TEENSY3.1") (pin "19/A5") (pinfunction "19/A5/T/SCL0_19/A5") (pintype "bidirectional"))
    )
    (net (code "9") (name "CV2") (class "Default")
      (node (ref "R65") (pin "2") (pinfunction "2_2") (pintype "passive"))
      (node (ref "TEENSY3.1") (pin "18/A4") (pinfunction "18/A4/T/SDA0_18/A4") (pintype "bidirectional"))
    )
    (net (code "10") (name "CV3") (class "Default")
      (node (ref "R69") (pin "2") (pinfunction "2_2") (pintype "passive"))
      (node (ref "TEENSY3.1") (pin "20/A6") (pinfunction "20/A6/PWM_20/A6") (pintype "bidirectional"))
    )
    (net (code "11") (name "CV4") (class "Default")
      (node (ref "R73") (pin "2") (pinfunction "2_2") (pintype "passive"))
      (node (ref "TEENSY3.1") (pin "17/A3") (pinfunction "17/A3/T_17/A3") (pintype "bidirectional"))
    )
    (net (code "12") (name "CV_A") (class "Default")
      (node (ref "DAC") (pin "1") (pinfunction "VOUTA_1") (pintype "output"))
      (node (ref "R54") (pin "1") (pinfunction "1_1") (pintype "passive"))
    )
    (net (code "13") (name "CV_B") (class "Default")
      (node (ref "DAC") (pin "2") (pinfunction "VOUTB_2") (pintype "output"))
      (node (ref "R57") (pin "1") (pinfunction "1_1") (pintype "passive"))
    )
    (net (code "14") (name "CV_C") (class "Default")
      (node (ref "DAC") (pin "7") (pinfunction "VOUTC_7") (pintype "output"))
      (node (ref "R48") (pin "1") (pinfunction "1_1") (pintype "passive"))
    )
    (net (code "15") (name "CV_D") (class "Default")
      (node (ref "DAC") (pin "8") (pinfunction "VOUTD_8") (pintype "output"))
      (node (ref "R51") (pin "1") (pinfunction "1_1") (pintype "passive"))
    )
    (net (code "16") (name "DC") (class "Default")
      (node (ref "JP2") (pin "6") (pinfunction "6_6") (pintype "passive"))
      (node (ref "TEENSY3.1") (pin "6") (pinfunction "6/PWM_6") (pintype "bidirectional"))
    )
    (net (code "17") (name "DOUT") (class "Default")
      (node (ref "DAC") (pin "11") (pinfunction "DIN_11") (pintype "input"))
      (node (ref "JP2") (pin "4") (pinfunction "4_4") (pintype "passive"))
      (node (ref "TEENSY3.1") (pin "11") (pinfunction "11/MOSI_11") (pintype "bidirectional"))
    )
    (net (code "18") (name "ENC_L1") (class "Default")
      (node (ref "SW_L") (pin "B") (pinfunction "B_B") (pintype "passive"))
      (node (ref "TEENSY3.1") (pin "22/A8") (pinfunction "22/A8/T/PWM_22/A8") (pintype "bidirectional"))
    )
    (net (code "19") (name "ENC_L2") (class "Default")
      (node (ref "SW_L") (pin "A") (pinfunction "A_A") (pintype "passive"))
      (node (ref "TEENSY3.1") (pin "21/A7") (pinfunction "21/A7/PWM_21/A7") (pintype "bidirectional"))
    )
    (net (code "20") (name "ENC_R1") (class "Default")
      (node (ref "SW_R") (pin "B") (pinfunction "B_B") (pintype "passive"))
      (node (ref "TEENSY3.1") (pin "15/A1") (pinfunction "15/A1/T_15/A1") (pintype "bidirectional"))
    )
    (net (code "21") (name "ENC_R2") (class "Default")
      (node (ref "SW_R") (pin "A") (pinfunction "A_A") (pintype "passive"))
      (node (ref "TEENSY3.1") (pin "16/A2") (pinfunction "16/A2/T_16/A2") (pintype "bidirectional"))
    )
    (net (code "22") (name "GND") (class "Default")
      (node (ref "C38") (pin "2") (pinfunction "2_2") (pintype "passive"))
      (node (ref "C39") (pin "2") (pinfunction "2_2") (pintype "passive"))
      (node (ref "C40") (pin "2") (pinfunction "2_2") (pintype "passive"))
      (node (ref "C41") (pin "2") (pinfunction "2_2") (pintype "passive"))
      (node (ref "C42") (pin "2") (pinfunction "2_2") (pintype "passive"))
      (node (ref "C43") (pin "2") (pinfunction "2_2") (pintype "passive"))
      (node (ref "C48") (pin "2") (pinfunction "2_2") (pintype "passive"))
      (node (ref "C49") (pin "2") (pinfunction "2_2") (pintype "passive"))
      (node (ref "C50") (pin "2") (pinfunction "2_2") (pintype "passive"))
      (node (ref "C51") (pin "2") (pinfunction "2_2") (pintype "passive"))
      (node (ref "C56") (pin "2") (pinfunction "2_2") (pintype "passive"))
      (node (ref "C57") (pin "2") (pinfunction "2_2") (pintype "passive"))
      (node (ref "C58") (pin "2") (pinfunction "2_2") (pintype "passive"))
      (node (ref "C59") (pin "1") (pinfunction "1_1") (pintype "passive"))
      (node (ref "C60") (pin "2") (pinfunction "2_2") (pintype "passive"))
      (node (ref "C61") (pin "2") (pinfunction "2_2") (pintype "passive"))
      (node (ref "C62") (pin "2") (pinfunction "2_2") (pintype "passive"))
      (node (ref "C63") (pin "1") (pinfunction "1_1") (pintype "passive"))
      (node (ref "C64") (pin "2") (pinfunction "2_2") (pintype "passive"))
      (node (ref "C65") (pin "2") (pinfunction "2_2") (pintype "passive"))
      (node (ref "C66") (pin "2") (pinfunction "2_2") (pintype "passive"))
      (node (ref "C74") (pin "-") (pinfunction "-_-") (pintype "passive"))
      (node (ref "C75") (pin "+") (pinfunction "+_+") (pintype "passive"))
      (node (ref "C76") (pin "2") (pinfunction "2_2") (pintype "passive"))
      (node (ref "C77") (pin "1") (pinfunction "1_1") (pintype "passive"))
      (node (ref "C78") (pin "2") (pinfunction "2_2") (pintype "passive"))
      (node (ref "C79") (pin "1") (pinfunction "1_1") (pintype "passive"))
      (node (ref "C9") (pin "2") (pinfunction "2_2") (pintype "passive"))
      (node (ref "D1") (pin "A") (pinfunction "A_A") (pintype "passive"))
      (node (ref "D2") (pin "A") (pinfunction "A_A") (pintype "passive"))
      (node (ref "D3") (pin "A") (pinfunction "A_A") (pintype "passive"))
      (node (ref "D4") (pin "A") (pinfunction "A_A") (pintype "passive"))
      (node (ref "DAC") (pin "14") (pinfunction "RSTSEL_14") (pintype "input"))
      (node (ref "DAC") (pin "15") (pinfunction "~{ENABLE}_15") (pintype "input"))
      (node (ref "DAC") (pin "16") (pinfunction "LDAC_16") (pintype "input"))
      (node (ref "DAC") (pin "5") (pinfunction "VREFL_5") (pintype "input"))
      (node (ref "DAC") (pin "6") (pinfunction "GND_6") (pintype "passive"))
      (node (ref "DOWNSW1") (pin "1") (pinfunction "1_1") (pintype "passive"))
      (node (ref "DOWNSW1") (pin "2") (pinfunction "2_2") (pintype "passive"))
      (node (ref "IC11") (pin "3") (pinfunction "+IN_3") (pintype "input"))
      (node (ref "IC11") (pin "4") (pinfunction "V-_4") (pintype "power_in"))
      (node (ref "IC11") (pin "5") (pinfunction "+IN_5") (pintype "input"))
      (node (ref "IC7") (pin "1") (pinfunction "GND_1") (pintype "input"))
      (node (ref "IC8") (pin "3") (pinfunction "+IN_3") (pintype "input"))
      (node (ref "IC8") (pin "4") (pinfunction "V-_4") (pintype "power_in"))
      (node (ref "IC8") (pin "5") (pinfunction "+IN_5") (pintype "input"))
      (node (ref "IC9") (pin "1") (pinfunction "C_1") (pintype "passive"))
      (node (ref "J2") (pin "2") (pinfunction "2_2") (pintype "passive"))
      (node (ref "J2") (pin "3") (pinfunction "3_3") (pintype "passive"))
      (node (ref "J3") (pin "2") (pinfunction "3_2") (pintype "bidirectional"))
      (node (ref "J3") (pin "3") (pinfunction "2_3") (pintype "bidirectional"))
      (node (ref "JP2") (pin "1") (pinfunction "1_1") (pintype "passive"))
      (node (ref "R59") (pin "1") (pinfunction "1_1") (pintype "passive"))
      (node (ref "R78") (pin "1") (pinfunction "1_1") (pintype "passive"))
      (node (ref "R80") (pin "1") (pinfunction "1_1") (pintype "passive"))
      (node (ref "R82") (pin "1") (pinfunction "1_1") (pintype "passive"))
      (node (ref "R84") (pin "1") (pinfunction "1_1") (pintype "passive"))
      (node (ref "SW_L") (pin "C") (pinfunction "C_C") (pintype "passive"))
      (node (ref "SW_L") (pin "D") (pinfunction "1_D") (pintype "passive"))
      (node (ref "SW_R") (pin "C") (pinfunction "C_C") (pintype "passive"))
      (node (ref "SW_R") (pin "D") (pinfunction "1_D") (pintype "passive"))
      (node (ref "T5") (pin "E") (pinfunction "E_E") (pintype "passive"))
      (node (ref "T6") (pin "E") (pinfunction "E_E") (pintype "passive"))
      (node (ref "T7") (pin "E") (pinfunction "E_E") (pintype "passive"))
      (node (ref "T8") (pin "E") (pinfunction "E_E") (pintype "passive"))
      (node (ref "TEENSY3.1") (pin "AGND") (pinfunction "AGND_AGND") (pintype "power_in"))
      (node (ref "TEENSY3.1") (pin "GND") (pinfunction "GND_GND") (pintype "power_in"))
      (node (ref "U1") (pin "1") (pinfunction "GND_1") (pintype "passive"))
      (node (ref "U3") (pin "2") (pinfunction "GND_2") (pintype "bidirectional"))
      (node (ref "UPSW1") (pin "1") (pinfunction "1_1") (pintype "passive"))
      (node (ref "UPSW1") (pin "2") (pinfunction "2_2") (pintype "passive"))
    )
    (net (code "23") (name "Net-(A-1)") (class "Default")
      (node (ref "A") (pin "P$1") (pinfunction "1_P$1") (pintype "passive"))
      (node (ref "CV_A1") (pin "1") (pinfunction "1_1") (pintype "passive"))
      (node (ref "R52") (pin "2") (pinfunction "2_2") (pintype "passive"))
      (node (ref "R53") (pin "2") (pinfunction "2_2") (pintype "passive"))
    )
    (net (code "24") (name "Net-(B-1)") (class "Default")
      (node (ref "B") (pin "P$1") (pinfunction "1_P$1") (pintype "passive"))
      (node (ref "CV_B1") (pin "1") (pinfunction "1_1") (pintype "passive"))
      (node (ref "R55") (pin "2") (pinfunction "2_2") (pintype "passive"))
      (node (ref "R56") (pin "2") (pinfunction "2_2") (pintype "passive"))
    )
    (net (code "25") (name "Net-(C-1)") (class "Default")
      (node (ref "C") (pin "P$1") (pinfunction "1_P$1") (pintype "passive"))
      (node (ref "CV_C1") (pin "1") (pinfunction "1_1") (pintype "passive"))
      (node (ref "R46") (pin "2") (pinfunction "2_2") (pintype "passive"))
      (node (ref "R47") (pin "2") (pinfunction "2_2") (pintype "passive"))
    )
    (net (code "26") (name "Net-(CV1-1)") (class "Default")
      (node (ref "CV1") (pin "P$1") (pinfunction "1_P$1") (pintype "passive"))
      (node (ref "CVIN5") (pin "1") (pinfunction "1_1") (pintype "passive"))
      (node (ref "R62") (pin "1") (pinfunction "1_1") (pintype "passive"))
    )
    (net (code "27") (name "Net-(CV2-1)") (class "Default")
      (node (ref "CV2") (pin "P$1") (pinfunction "1_P$1") (pintype "passive"))
      (node (ref "CVIN6") (pin "1") (pinfunction "1_1") (pintype "passive"))
      (node (ref "R66") (pin "1") (pinfunction "1_1") (pintype "passive"))
    )
    (net (code "28") (name "Net-(CV3-1)") (class "Default")
      (node (ref "CV3") (pin "P$1") (pinfunction "1_P$1") (pintype "passive"))
      (node (ref "CVIN7") (pin "1") (pinfunction "1_1") (pintype "passive"))
      (node (ref "R70") (pin "1") (pinfunction "1_1") (pintype "passive"))
    )
    (net (code "29") (name "Net-(CV4-1)") (class "Default")
      (node (ref "CV4") (pin "P$1") (pinfunction "1_P$1") (pintype "passive"))
      (node (ref "CVIN8") (pin "1") (pinfunction "1_1") (pintype "passive"))
      (node (ref "R74") (pin "1") (pinfunction "1_1") (pintype "passive"))
    )
    (net (code "30") (name "Net-(D-1)") (class "Default")
      (node (ref "CV_D1") (pin "1") (pinfunction "1_1") (pintype "passive"))
      (node (ref "D") (pin "P$1") (pinfunction "1_P$1") (pintype "passive"))
      (node (ref "R49") (pin "2") (pinfunction "2_2") (pintype "passive"))
      (node (ref "R50") (pin "2") (pinfunction "2_2") (pintype "passive"))
    )
    (net (code "31") (name "Net-(D1-PadC)") (class "Default")
      (node (ref "D1") (pin "C") (pinfunction "C_C") (pintype "passive"))
      (node (ref "R83") (pin "2") (pinfunction "2_2") (pintype "passive"))
      (node (ref "R84") (pin "2") (pinfunction "2_2") (pintype "passive"))
      (node (ref "T8") (pin "B") (pinfunction "B_B") (pintype "passive"))
    )
    (net (code "32") (name "Net-(D2-PadC)") (class "Default")
      (node (ref "D2") (pin "C") (pinfunction "C_C") (pintype "passive"))
      (node (ref "R81") (pin "2") (pinfunction "2_2") (pintype "passive"))
      (node (ref "R82") (pin "2") (pinfunction "2_2") (pintype "passive"))
      (node (ref "T7") (pin "B") (pinfunction "B_B") (pintype "passive"))
    )
    (net (code "33") (name "Net-(D3-PadC)") (class "Default")
      (node (ref "D3") (pin "C") (pinfunction "C_C") (pintype "passive"))
      (node (ref "R79") (pin "2") (pinfunction "2_2") (pintype "passive"))
      (node (ref "R80") (pin "2") (pinfunction "2_2") (pintype "passive"))
      (node (ref "T6") (pin "B") (pinfunction "B_B") (pintype "passive"))
    )
    (net (code "34") (name "Net-(D4-PadC)") (class "Default")
      (node (ref "D4") (pin "C") (pinfunction "C_C") (pintype "passive"))
      (node (ref "R77") (pin "2") (pinfunction "2_2") (pintype "passive"))
      (node (ref "R78") (pin "2") (pinfunction "2_2") (pintype "passive"))
      (node (ref "T5") (pin "B") (pinfunction "B_B") (pintype "passive"))
    )
    (net (code "35") (name "Net-(DOWNSW1-Pad3)") (class "Default")
      (node (ref "DOWNSW1") (pin "3") (pinfunction "3_3") (pintype "passive"))
      (node (ref "DOWNSW1") (pin "4") (pinfunction "4_4") (pintype "passive"))
      (node (ref "R86") (pin "1") (pinfunction "1_1") (pintype "passive"))
    )
    (net (code "36") (name "Net-(IC7-OUT)") (class "Default")
      (node (ref "C42") (pin "1") (pinfunction "1_1") (pintype "passive"))
      (node (ref "IC7") (pin "3") (pinfunction "OUT_3") (pintype "passive"))
      (node (ref "L2") (pin "1") (pinfunction "1_1") (pintype "passive"))
    )
    (net (code "37") (name "Net-(IC8A--IN)") (class "Default")
      (node (ref "C55") (pin "1") (pinfunction "1_1") (pintype "passive"))
      (node (ref "IC8") (pin "2") (pinfunction "-IN_2") (pintype "input"))
      (node (ref "R72") (pin "1") (pinfunction "1_1") (pintype "passive"))
      (node (ref "R74") (pin "2") (pinfunction "2_2") (pintype "passive"))
      (node (ref "R75") (pin "2") (pinfunction "2_2") (pintype "passive"))
    )
    (net (code "38") (name "Net-(IC8A-OUT)") (class "Default")
      (node (ref "C55") (pin "2") (pinfunction "2_2") (pintype "passive"))
      (node (ref "IC8") (pin "1") (pinfunction "OUT_1") (pintype "output"))
      (node (ref "R72") (pin "2") (pinfunction "2_2") (pintype "passive"))
      (node (ref "R73") (pin "1") (pinfunction "1_1") (pintype "passive"))
    )
    (net (code "39") (name "Net-(IC8B--IN)") (class "Default")
      (node (ref "C54") (pin "1") (pinfunction "1_1") (pintype "passive"))
      (node (ref "IC8") (pin "6") (pinfunction "-IN_6") (pintype "input"))
      (node (ref "R68") (pin "1") (pinfunction "1_1") (pintype "passive"))
      (node (ref "R70") (pin "2") (pinfunction "2_2") (pintype "passive"))
      (node (ref "R71") (pin "2") (pinfunction "2_2") (pintype "passive"))
    )
    (net (code "40") (name "Net-(IC8B-OUT)") (class "Default")
      (node (ref "C54") (pin "2") (pinfunction "2_2") (pintype "passive"))
      (node (ref "IC8") (pin "7") (pinfunction "OUT_7") (pintype "output"))
      (node (ref "R68") (pin "2") (pinfunction "2_2") (pintype "passive"))
      (node (ref "R69") (pin "1") (pinfunction "1_1") (pintype "passive"))
    )
    (net (code "41") (name "Net-(IC10A--IN)") (class "Default")
      (node (ref "C46") (pin "1") (pinfunction "1_1") (pintype "passive"))
      (node (ref "IC10") (pin "2") (pinfunction "-IN_2") (pintype "input"))
      (node (ref "R53") (pin "1") (pinfunction "1_1") (pintype "passive"))
      (node (ref "R54") (pin "2") (pinfunction "2_2") (pintype "passive"))
    )
    (net (code "42") (name "Net-(IC10A-OUT)") (class "Default")
      (node (ref "C46") (pin "2") (pinfunction "2_2") (pintype "passive"))
      (node (ref "IC10") (pin "1") (pinfunction "OUT_1") (pintype "output"))
      (node (ref "R52") (pin "1") (pinfunction "1_1") (pintype "passive"))
    )
    (net (code "43") (name "Net-(IC10B--IN)") (class "Default")
      (node (ref "C44") (pin "1") (pinfunction "1_1") (pintype "passive"))
      (node (ref "IC10") (pin "6") (pinfunction "-IN_6") (pintype "input"))
      (node (ref "R47") (pin "1") (pinfunction "1_1") (pintype "passive"))
      (node (ref "R48") (pin "2") (pinfunction "2_2") (pintype "passive"))
    )
    (net (code "44") (name "Net-(IC10B-OUT)") (class "Default")
      (node (ref "C44") (pin "2") (pinfunction "2_2") (pintype "passive"))
      (node (ref "IC10") (pin "7") (pinfunction "OUT_7") (pintype "output"))
      (node (ref "R46") (pin "1") (pinfunction "1_1") (pintype "passive"))
    )
    (net (code "45") (name "Net-(IC10C--IN)") (class "Default")
      (node (ref "C45") (pin "1") (pinfunction "1_1") (pintype "passive"))
      (node (ref "IC10") (pin "9") (pinfunction "-IN_9") (pintype "input"))
      (node (ref "R50") (pin "1") (pinfunction "1_1") (pintype "passive"))
      (node (ref "R51") (pin "2") (pinfunction "2_2") (pintype "passive"))
    )
    (net (code "46") (name "Net-(IC10C-OUT)") (class "Default")
      (node (ref "C45") (pin "2") (pinfunction "2_2") (pintype "passive"))
      (node (ref "IC10") (pin "8") (pinfunction "OUT_8") (pintype "output"))
      (node (ref "R49") (pin "1") (pinfunction "1_1") (pintype "passive"))
    )
    (net (code "47") (name "Net-(IC10D--IN)") (class "Default")
      (node (ref "C47") (pin "1") (pinfunction "1_1") (pintype "passive"))
      (node (ref "IC10") (pin "13") (pinfunction "-IN_13") (pintype "input"))
      (node (ref "R56") (pin "1") (pinfunction "1_1") (pintype "passive"))
      (node (ref "R57") (pin "2") (pinfunction "2_2") (pintype "passive"))
    )
    (net (code "48") (name "Net-(IC10D-OUT)") (class "Default")
      (node (ref "C47") (pin "2") (pinfunction "2_2") (pintype "passive"))
      (node (ref "IC10") (pin "14") (pinfunction "OUT_14") (pintype "output"))
      (node (ref "R55") (pin "1") (pinfunction "1_1") (pintype "passive"))
    )
    (net (code "49") (name "Net-(IC11A--IN)") (class "Default")
      (node (ref "C52") (pin "1") (pinfunction "1_1") (pintype "passive"))
      (node (ref "IC11") (pin "2") (pinfunction "-IN_2") (pintype "input"))
      (node (ref "R60") (pin "1") (pinfunction "1_1") (pintype "passive"))
      (node (ref "R62") (pin "2") (pinfunction "2_2") (pintype "passive"))
      (node (ref "R63") (pin "2") (pinfunction "2_2") (pintype "passive"))
    )
    (net (code "50") (name "Net-(IC11A-OUT)") (class "Default")
      (node (ref "C52") (pin "2") (pinfunction "2_2") (pintype "passive"))
      (node (ref "IC11") (pin "1") (pinfunction "OUT_1") (pintype "output"))
      (node (ref "R60") (pin "2") (pinfunction "2_2") (pintype "passive"))
      (node (ref "R61") (pin "1") (pinfunction "1_1") (pintype "passive"))
    )
    (net (code "51") (name "Net-(IC11B--IN)") (class "Default")
      (node (ref "C53") (pin "1") (pinfunction "1_1") (pintype "passive"))
      (node (ref "IC11") (pin "6") (pinfunction "-IN_6") (pintype "input"))
      (node (ref "R64") (pin "1") (pinfunction "1_1") (pintype "passive"))
      (node (ref "R66") (pin "2") (pinfunction "2_2") (pintype "passive"))
      (node (ref "R67") (pin "2") (pinfunction "2_2") (pintype "passive"))
    )
    (net (code "52") (name "Net-(IC11B-OUT)") (class "Default")
      (node (ref "C53") (pin "2") (pinfunction "2_2") (pintype "passive"))
      (node (ref "IC11") (pin "7") (pinfunction "OUT_7") (pintype "output"))
      (node (ref "R64") (pin "2") (pinfunction "2_2") (pintype "passive"))
      (node (ref "R65") (pin "1") (pinfunction "1_1") (pintype "passive"))
    )
    (net (code "53") (name "Net-(J3-1)") (class "Default")
      (node (ref "D11") (pin "C") (pinfunction "C_C") (pintype "passive"))
      (node (ref "J2") (pin "4") (pinfunction "4_4") (pintype "passive"))
      (node (ref "J3") (pin "4") (pinfunction "1_4") (pintype "bidirectional"))
    )
    (net (code "54") (name "Net-(J3-4)") (class "Default")
      (node (ref "D9") (pin "A") (pinfunction "A_A") (pintype "passive"))
      (node (ref "J2") (pin "1") (pinfunction "1_1") (pintype "passive"))
      (node (ref "J3") (pin "1") (pinfunction "4_1") (pintype "bidirectional"))
    )
    (net (code "55") (name "Net-(R85-Pad1)") (class "Default")
      (node (ref "R85") (pin "1") (pinfunction "1_1") (pintype "passive"))
      (node (ref "UPSW1") (pin "3") (pinfunction "3_3") (pintype "passive"))
      (node (ref "UPSW1") (pin "4") (pinfunction "4_4") (pintype "passive"))
    )
    (net (code "56") (name "Net-(TRIG1-1)") (class "Default")
      (node (ref "R77") (pin "1") (pinfunction "1_1") (pintype "passive"))
      (node (ref "TR5") (pin "1") (pinfunction "1_1") (pintype "passive"))
      (node (ref "TRIG1") (pin "P$1") (pinfunction "1_P$1") (pintype "passive"))
    )
    (net (code "57") (name "Net-(TRIG2-1)") (class "Default")
      (node (ref "R79") (pin "1") (pinfunction "1_1") (pintype "passive"))
      (node (ref "TR6") (pin "1") (pinfunction "1_1") (pintype "passive"))
      (node (ref "TRIG2") (pin "P$1") (pinfunction "1_P$1") (pintype "passive"))
    )
    (net (code "58") (name "Net-(TRIG3-1)") (class "Default")
      (node (ref "R81") (pin "1") (pinfunction "1_1") (pintype "passive"))
      (node (ref "TR7") (pin "1") (pinfunction "1_1") (pintype "passive"))
      (node (ref "TRIG3") (pin "P$1") (pinfunction "1_P$1") (pintype "passive"))
    )
    (net (code "59") (name "Net-(TRIG4-1)") (class "Default")
      (node (ref "R83") (pin "1") (pinfunction "1_1") (pintype "passive"))
      (node (ref "TR8") (pin "1") (pinfunction "1_1") (pintype "passive"))
      (node (ref "TRIG4") (pin "P$1") (pinfunction "1_P$1") (pintype "passive"))
    )
    (net (code "60") (name "OFFSET") (class "Default")
      (node (ref "C56") (pin "1") (pinfunction "1_1") (pintype "passive"))
      (node (ref "IC9") (pin "2") (pinfunction "A_2") (pintype "passive"))
      (node (ref "R63") (pin "1") (pinfunction "1_1") (pintype "passive"))
      (node (ref "R67") (pin "1") (pinfunction "1_1") (pintype "passive"))
      (node (ref "R71") (pin "1") (pinfunction "1_1") (pintype "passive"))
      (node (ref "R75") (pin "1") (pinfunction "1_1") (pintype "passive"))
      (node (ref "R76") (pin "1") (pinfunction "1_1") (pintype "passive"))
    )
    (net (code "61") (name "POGO") (class "Default")
      (node (ref "R1") (pin "1") (pinfunction "1_1") (pintype "passive"))
      (node (ref "U1") (pin "2") (pinfunction "~{RESET}_2") (pintype "passive"))
    )
    (net (code "62") (name "RST") (class "Default")
      (node (ref "JP2") (pin "5") (pinfunction "5_5") (pintype "passive"))
      (node (ref "TEENSY3.1") (pin "7") (pinfunction "7/RX3_7") (pintype "bidirectional"))
    )
    (net (code "63") (name "RST_DAC") (class "Default")
      (node (ref "DAC") (pin "13") (pinfunction "~{RST}_13") (pintype "input"))
      (node (ref "TEENSY3.1") (pin "9") (pinfunction "9/RX2/PWM_9") (pintype "bidirectional"))
    )
    (net (code "64") (name "SCK") (class "Default")
      (node (ref "DAC") (pin "10") (pinfunction "SCLK_10") (pintype "input"))
      (node (ref "JP2") (pin "3") (pinfunction "3_3") (pintype "passive"))
      (node (ref "TEENSY3.1") (pin "13") (pinfunction "13/SCK/LED_13") (pintype "bidirectional"))
    )
    (net (code "65") (name "SW_B") (class "Default")
      (node (ref "C58") (pin "1") (pinfunction "1_1") (pintype "passive"))
      (node (ref "R86") (pin "2") (pinfunction "2_2") (pintype "passive"))
      (node (ref "TEENSY3.1") (pin "4") (pinfunction "4/CAN-RX/PWM_4") (pintype "bidirectional"))
    )
    (net (code "66") (name "SW_L") (class "Default")
      (node (ref "C51") (pin "1") (pinfunction "1_1") (pintype "passive"))
      (node (ref "SW_L") (pin "E") (pinfunction "2_E") (pintype "passive"))
      (node (ref "TEENSY3.1") (pin "23/A9") (pinfunction "23/A9/T/PWM_23/A9") (pintype "bidirectional"))
    )
    (net (code "67") (name "SW_R") (class "Default")
      (node (ref "SW_R") (pin "E") (pinfunction "2_E") (pintype "passive"))
      (node (ref "TEENSY3.1") (pin "14/A0") (pinfunction "14/A1_14/A0") (pintype "bidirectional"))
    )
    (net (code "68") (name "SW_T") (class "Default")
      (node (ref "C59") (pin "2") (pinfunction "2_2") (pintype "passive"))
      (node (ref "R85") (pin "2") (pinfunction "2_2") (pintype "passive"))
      (node (ref "TEENSY3.1") (pin "5") (pinfunction "5/PWM_5") (pintype "bidirectional"))
    )
    (net (code "69") (name "TR1") (class "Default")
      (node (ref "T5") (pin "C") (pinfunction "C_C") (pintype "passive"))
      (node (ref "TEENSY3.1") (pin "0") (pinfunction "0/RX1/T_0") (pintype "bidirectional"))
    )
    (net (code "70") (name "TR2") (class "Default")
      (node (ref "T6") (pin "C") (pinfunction "C_C") (pintype "passive"))
      (node (ref "TEENSY3.1") (pin "1") (pinfunction "1/TX1/T_1") (pintype "bidirectional"))
    )
    (net (code "71") (name "TR3") (class "Default")
      (node (ref "T7") (pin "C") (pinfunction "C_C") (pintype "passive"))
      (node (ref "TEENSY3.1") (pin "2") (pinfunction "2_2") (pintype "bidirectional"))
    )
    (net (code "72") (name "TR4") (class "Default")
      (node (ref "T8") (pin "C") (pinfunction "C_C") (pintype "passive"))
      (node (ref "TEENSY3.1") (pin "3") (pinfunction "3/CAN-TX/PWM_3") (pintype "bidirectional"))
    )
    (net (code "73") (name "UNUSED") (class "Default")
      (node (ref "TEENSY3.1") (pin "12") (pinfunction "12/MISO_12") (pintype "bidirectional"))
    )
    (net (code "74") (name "VREF_2V5") (class "Default")
      (node (ref "C48") (pin "1") (pinfunction "1_1") (pintype "passive"))
      (node (ref "C49") (pin "1") (pinfunction "1_1") (pintype "passive"))
      (node (ref "DAC") (pin "3") (pinfunction "VREFH/VREFOUT_3") (pintype "bidirectional"))
      (node (ref "R58") (pin "2") (pinfunction "2_2") (pintype "passive"))
    )
    (net (code "75") (name "V_BIAS") (class "Default")
      (node (ref "C50") (pin "1") (pinfunction "1_1") (pintype "passive"))
      (node (ref "IC10") (pin "10") (pinfunction "+IN_10") (pintype "input"))
      (node (ref "IC10") (pin "12") (pinfunction "+IN_12") (pintype "input"))
      (node (ref "IC10") (pin "3") (pinfunction "+IN_3") (pintype "input"))
      (node (ref "IC10") (pin "5") (pinfunction "+IN_5") (pintype "input"))
      (node (ref "R58") (pin "1") (pinfunction "1_1") (pintype "passive"))
      (node (ref "R59") (pin "2") (pinfunction "2_2") (pintype "passive"))
    )
  )
)
